# Rocket_PCB_true.net
KiCad netlist of a schematic drawn in EAGLE
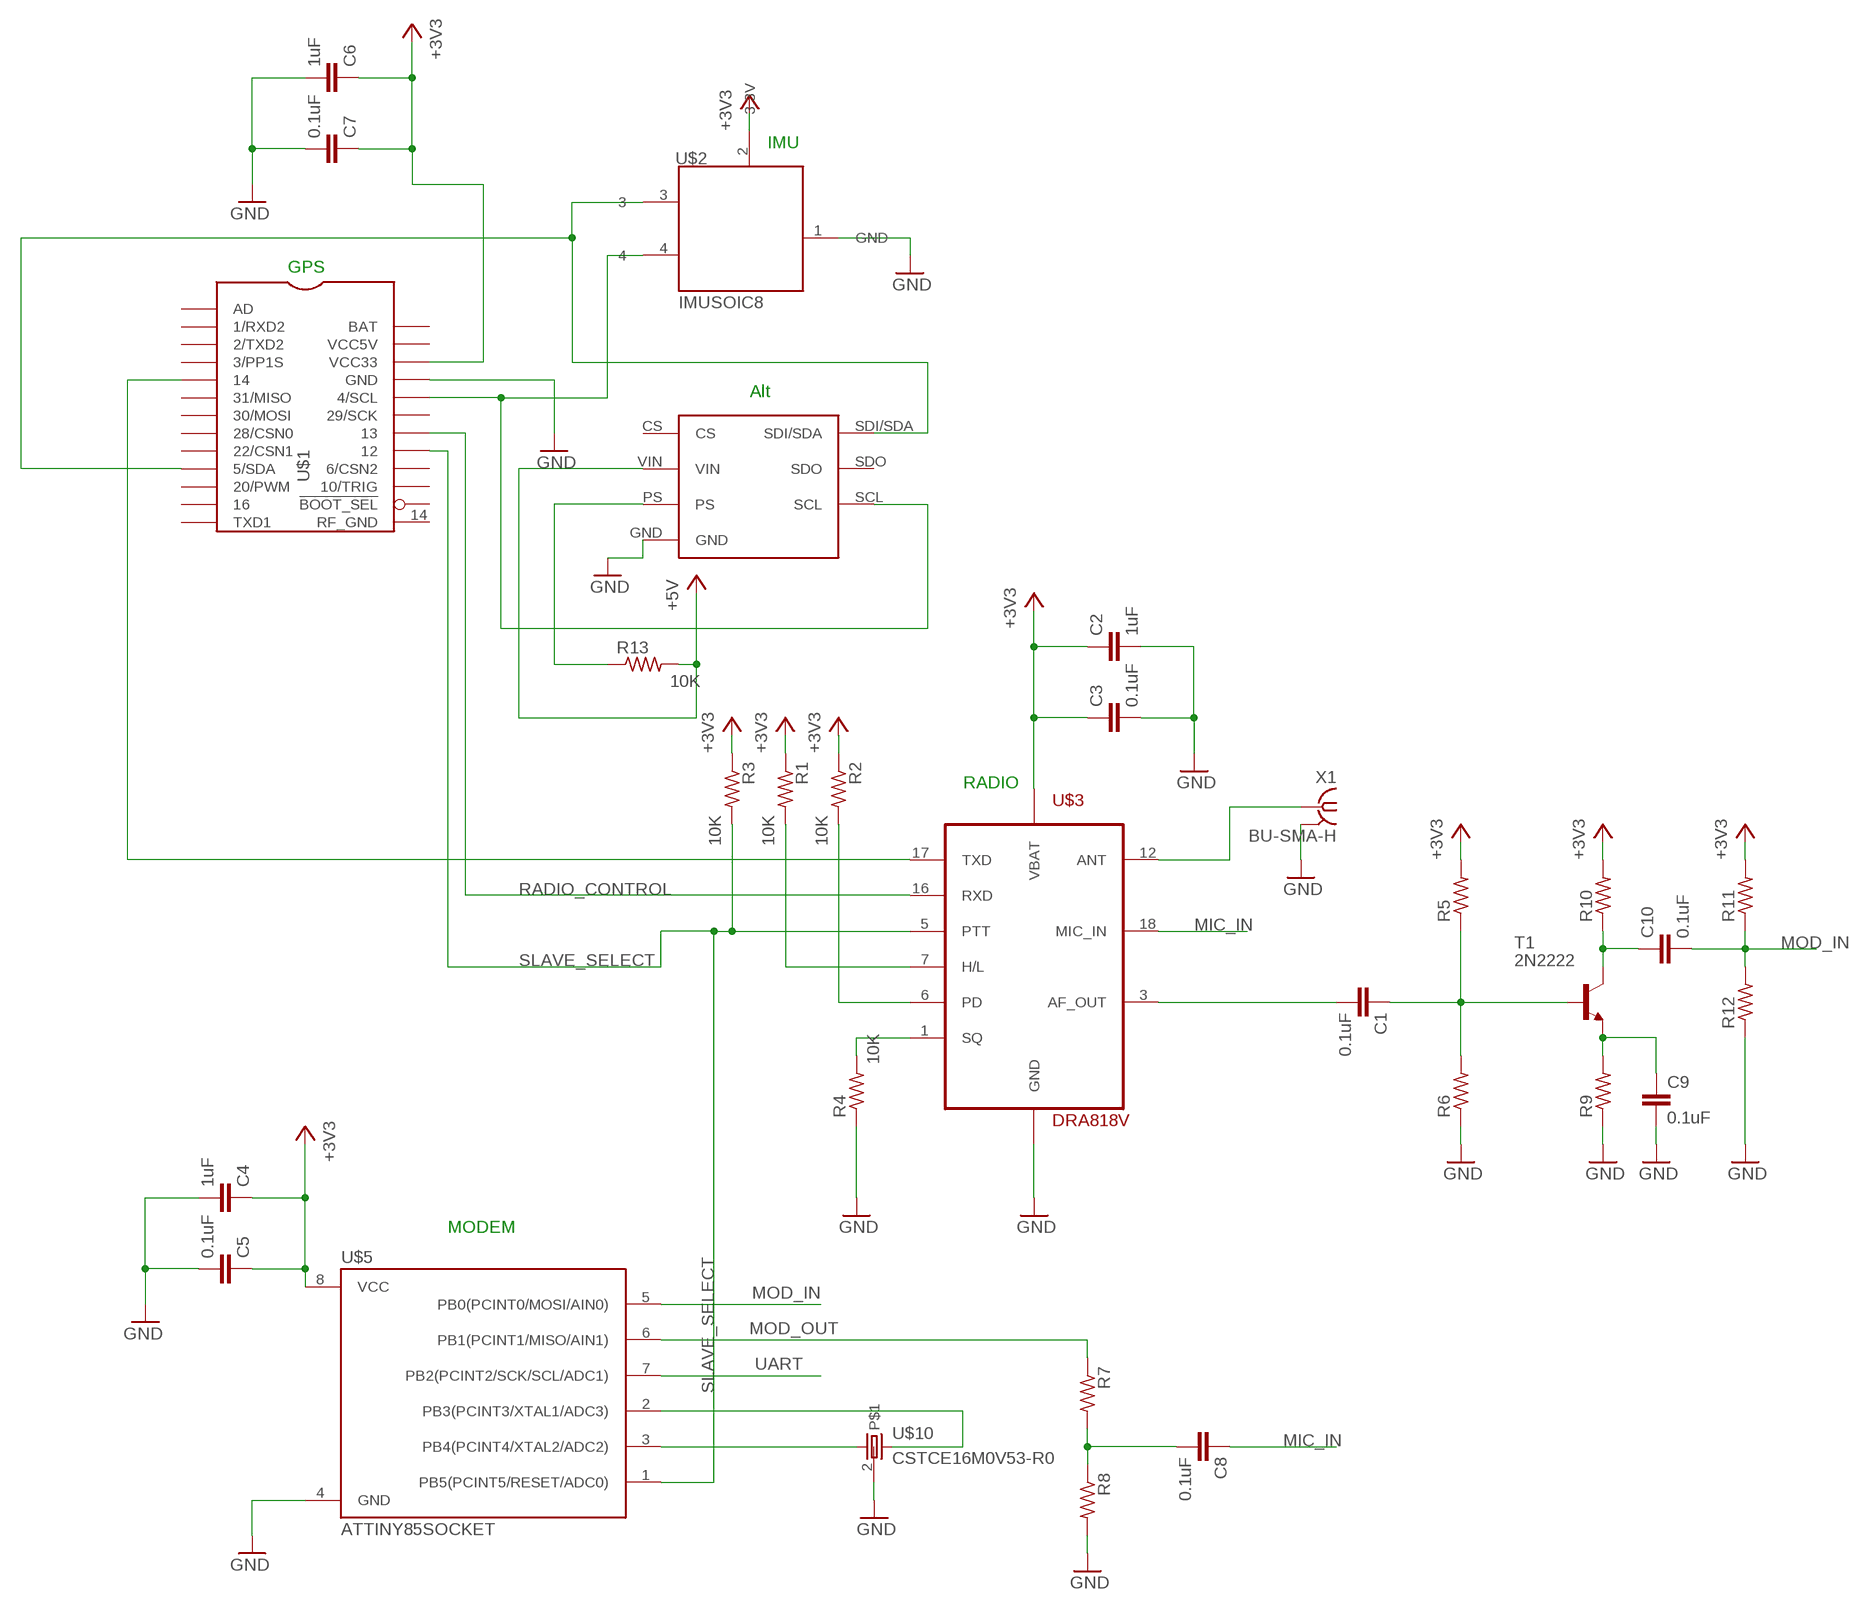
[diagram p0: schematic, sheet 1]

(export (version "E")
  (design (tool "Eeschema 10.0.6"))
  (components
    (comp (ref "C1")
      (value "0.1uF")
      (footprint "eagle-import:C0603")
      (libsource (lib "eagle-import") (part "C-EUC0603"))
    )
    (comp (ref "C2")
      (value "1uF")
      (footprint "eagle-import:C0603")
      (libsource (lib "eagle-import") (part "C-EUC0603"))
    )
    (comp (ref "C3")
      (value "0.1uF")
      (footprint "eagle-import:C0603")
      (libsource (lib "eagle-import") (part "C-EUC0603"))
    )
    (comp (ref "C4")
      (value "1uF")
      (footprint "eagle-import:C0603")
      (libsource (lib "eagle-import") (part "C-EUC0603"))
    )
    (comp (ref "C5")
      (value "0.1uF")
      (footprint "eagle-import:C0603")
      (libsource (lib "eagle-import") (part "C-EUC0603"))
    )
    (comp (ref "C6")
      (value "1uF")
      (footprint "eagle-import:C0603")
      (libsource (lib "eagle-import") (part "C-EUC0603"))
    )
    (comp (ref "C7")
      (value "0.1uF")
      (footprint "eagle-import:C0603")
      (libsource (lib "eagle-import") (part "C-EUC0603"))
    )
    (comp (ref "C8")
      (value "0.1uF")
      (footprint "eagle-import:C0603")
      (libsource (lib "eagle-import") (part "C-EUC0603"))
    )
    (comp (ref "C9")
      (value "0.1uF")
      (footprint "eagle-import:C0603")
      (libsource (lib "eagle-import") (part "C-EUC0603"))
    )
    (comp (ref "C10")
      (value "0.1uF")
      (footprint "eagle-import:C0603")
      (libsource (lib "eagle-import") (part "C-EUC0603"))
    )
    (comp (ref "R1")
      (value "10K")
      (footprint "eagle-import:R0603")
      (libsource (lib "eagle-import") (part "R-US_R0603"))
    )
    (comp (ref "R2")
      (value "10K")
      (footprint "eagle-import:R0603")
      (libsource (lib "eagle-import") (part "R-US_R0603"))
    )
    (comp (ref "R3")
      (value "10K")
      (footprint "eagle-import:R0603")
      (libsource (lib "eagle-import") (part "R-US_R0603"))
    )
    (comp (ref "R4")
      (value "10K")
      (footprint "eagle-import:R0603")
      (libsource (lib "eagle-import") (part "R-US_R0603"))
    )
    (comp (ref "R5")
      (value "R-US_R0603")
      (footprint "eagle-import:R0603")
      (libsource (lib "eagle-import") (part "R-US_R0603"))
    )
    (comp (ref "R6")
      (value "R-US_R0603")
      (footprint "eagle-import:R0603")
      (libsource (lib "eagle-import") (part "R-US_R0603"))
    )
    (comp (ref "R7")
      (value "R-US_R0603")
      (footprint "eagle-import:R0603")
      (libsource (lib "eagle-import") (part "R-US_R0603"))
    )
    (comp (ref "R8")
      (value "R-US_R0603")
      (footprint "eagle-import:R0603")
      (libsource (lib "eagle-import") (part "R-US_R0603"))
    )
    (comp (ref "R9")
      (value "R-US_R0603")
      (footprint "eagle-import:R0603")
      (libsource (lib "eagle-import") (part "R-US_R0603"))
    )
    (comp (ref "R10")
      (value "R-US_R0603")
      (footprint "eagle-import:R0603")
      (libsource (lib "eagle-import") (part "R-US_R0603"))
    )
    (comp (ref "R11")
      (value "R-US_R0603")
      (footprint "eagle-import:R0603")
      (libsource (lib "eagle-import") (part "R-US_R0603"))
    )
    (comp (ref "R12")
      (value "R-US_R0603")
      (footprint "eagle-import:R0603")
      (libsource (lib "eagle-import") (part "R-US_R0603"))
    )
    (comp (ref "R13")
      (value "10K")
      (footprint "eagle-import:R0603")
      (libsource (lib "eagle-import") (part "R-US_R0603"))
    )
    (comp (ref "T1")
      (value "2N2222")
      (footprint "eagle-import:TO18")
      (libsource (lib "eagle-import") (part "2N2222"))
    )
    (comp (ref "U$1")
      (value "NAVSPARK_FULL")
      (footprint "eagle-import:NAVSPARK_FULL")
      (libsource (lib "eagle-import") (part "NAVSPARK_FULL"))
    )
    (comp (ref "U$2")
      (value "IMUSOIC8")
      (footprint "eagle-import:SO08")
      (libsource (lib "eagle-import") (part "IMUSOIC8"))
    )
    (comp (ref "U$3")
      (value "DRA818V")
      (footprint "eagle-import:DORJI")
      (libsource (lib "eagle-import") (part "DORJIDRA818V"))
    )
    (comp (ref "U$4")
      (value "MS-5607")
      (footprint "eagle-import:MS-5607")
      (libsource (lib "eagle-import") (part "MS-5607"))
    )
    (comp (ref "U$5")
      (value "ATTINY85SOCKET")
      (footprint "eagle-import:SOCKET-08")
      (libsource (lib "eagle-import") (part "ATTINY85SOCKET"))
    )
    (comp (ref "U$10")
      (value "CSTCE16M0V53-R0")
      (footprint "eagle-import:MYSMD2_RESONATOR")
      (libsource (lib "eagle-import") (part "CSTCE16M0V53-R0"))
    )
    (comp (ref "X1")
      (value "BU-SMA-H")
      (footprint "eagle-import:BU-SMA-H")
      (libsource (lib "eagle-import") (part "BU-SMA-H"))
    )
  )
  (nets
    (net (code "1") (name "+3V3") (class "Default")
      (node (ref "C2") (pin "1") (pinfunction "1_1") (pintype "passive"))
      (node (ref "C3") (pin "1") (pinfunction "1_1") (pintype "passive"))
      (node (ref "C4") (pin "1") (pinfunction "1_1") (pintype "passive"))
      (node (ref "C5") (pin "1") (pinfunction "1_1") (pintype "passive"))
      (node (ref "C6") (pin "1") (pinfunction "1_1") (pintype "passive"))
      (node (ref "C7") (pin "1") (pinfunction "1_1") (pintype "passive"))
      (node (ref "R1") (pin "1") (pinfunction "1_1") (pintype "passive"))
      (node (ref "R10") (pin "2") (pinfunction "2_2") (pintype "passive"))
      (node (ref "R11") (pin "2") (pinfunction "2_2") (pintype "passive"))
      (node (ref "R2") (pin "1") (pinfunction "1_1") (pintype "passive"))
      (node (ref "R3") (pin "1") (pinfunction "1_1") (pintype "passive"))
      (node (ref "R5") (pin "2") (pinfunction "2_2") (pintype "passive"))
      (node (ref "U$1") (pin "23") (pinfunction "VCC33_23") (pintype "power_in"))
      (node (ref "U$3") (pin "8") (pinfunction "VBAT_8") (pintype "bidirectional"))
      (node (ref "U$5") (pin "8") (pinfunction "VCC_8") (pintype "bidirectional"))
    )
    (net (code "2") (name "+5V") (class "Default")
      (node (ref "R13") (pin "2") (pinfunction "2_2") (pintype "passive"))
      (node (ref "U$4") (pin "VIN") (pinfunction "VIN_VIN") (pintype "bidirectional"))
    )
    (net (code "3") (name "/BAT") (class "Default")
      (node (ref "U$1") (pin "25") (pinfunction "BAT_25") (pintype "power_in"))
    )
    (net (code "4") (name "/MIC_IN") (class "Default")
      (node (ref "C8") (pin "1") (pinfunction "1_1") (pintype "passive"))
      (node (ref "U$3") (pin "18") (pinfunction "MIC_IN_18") (pintype "bidirectional"))
    )
    (net (code "5") (name "/MOD_IN") (class "Default")
      (node (ref "C10") (pin "2") (pinfunction "2_2") (pintype "passive"))
      (node (ref "R11") (pin "1") (pinfunction "1_1") (pintype "passive"))
      (node (ref "R12") (pin "2") (pinfunction "2_2") (pintype "passive"))
      (node (ref "U$5") (pin "5") (pinfunction "PB0(PCINT0/MOSI/AIN0)_5") (pintype "bidirectional"))
    )
    (net (code "6") (name "/MOD_OUT") (class "Default")
      (node (ref "R7") (pin "1") (pinfunction "1_1") (pintype "passive"))
      (node (ref "U$5") (pin "6") (pinfunction "PB1(PCINT1/MISO/AIN1)_6") (pintype "bidirectional"))
    )
    (net (code "7") (name "/RADIO_CONTROL") (class "Default")
      (node (ref "U$1") (pin "19") (pinfunction "13_19") (pintype "bidirectional"))
      (node (ref "U$3") (pin "16") (pinfunction "RXD_16") (pintype "bidirectional"))
    )
    (net (code "8") (name "/RF_GND") (class "Default")
      (node (ref "U$1") (pin "14") (pinfunction "RF_GND_14") (pintype "power_in"))
    )
    (net (code "9") (name "/SLAVE_SELECT") (class "Default")
      (node (ref "R3") (pin "2") (pinfunction "2_2") (pintype "passive"))
      (node (ref "U$1") (pin "18") (pinfunction "12_18") (pintype "bidirectional"))
      (node (ref "U$3") (pin "5") (pinfunction "PTT_5") (pintype "bidirectional"))
      (node (ref "U$5") (pin "1") (pinfunction "PB5(PCINT5/RESET/ADC0)_1") (pintype "bidirectional"))
    )
    (net (code "10") (name "/UART") (class "Default")
      (node (ref "U$5") (pin "7") (pinfunction "PB2(PCINT2/SCK/SCL/ADC1)_7") (pintype "bidirectional"))
    )
    (net (code "11") (name "/VCC5V") (class "Default")
      (node (ref "U$1") (pin "24") (pinfunction "VCC5V_24") (pintype "power_in"))
    )
    (net (code "12") (name "GND") (class "Default")
      (node (ref "C2") (pin "2") (pinfunction "2_2") (pintype "passive"))
      (node (ref "C3") (pin "2") (pinfunction "2_2") (pintype "passive"))
      (node (ref "C4") (pin "2") (pinfunction "2_2") (pintype "passive"))
      (node (ref "C5") (pin "2") (pinfunction "2_2") (pintype "passive"))
      (node (ref "C6") (pin "2") (pinfunction "2_2") (pintype "passive"))
      (node (ref "C7") (pin "2") (pinfunction "2_2") (pintype "passive"))
      (node (ref "C9") (pin "2") (pinfunction "2_2") (pintype "passive"))
      (node (ref "R12") (pin "1") (pinfunction "1_1") (pintype "passive"))
      (node (ref "R4") (pin "1") (pinfunction "1_1") (pintype "passive"))
      (node (ref "R6") (pin "1") (pinfunction "1_1") (pintype "passive"))
      (node (ref "R8") (pin "2") (pinfunction "2_2") (pintype "passive"))
      (node (ref "R9") (pin "1") (pinfunction "1_1") (pintype "passive"))
      (node (ref "U$1") (pin "22") (pinfunction "GND_22") (pintype "power_in"))
      (node (ref "U$10") (pin "2") (pinfunction "P$1_2") (pintype "bidirectional"))
      (node (ref "U$3") (pin "10") (pinfunction "GND_10") (pintype "bidirectional"))
      (node (ref "U$3") (pin "9") (pinfunction "GND_9") (pintype "bidirectional"))
      (node (ref "U$4") (pin "GND") (pinfunction "GND_GND") (pintype "bidirectional"))
      (node (ref "U$5") (pin "4") (pinfunction "GND_4") (pintype "bidirectional"))
      (node (ref "X1") (pin "2") (pinfunction "2_2") (pintype "passive"))
      (node (ref "X1") (pin "3") (pinfunction "2_3") (pintype "passive"))
      (node (ref "X1") (pin "4") (pinfunction "2_4") (pintype "passive"))
      (node (ref "X1") (pin "5") (pinfunction "2_5") (pintype "passive"))
    )
    (net (code "13") (name "Net-(C8-Pad2)") (class "Default")
      (node (ref "C8") (pin "2") (pinfunction "2_2") (pintype "passive"))
      (node (ref "R7") (pin "2") (pinfunction "2_2") (pintype "passive"))
      (node (ref "R8") (pin "1") (pinfunction "1_1") (pintype "passive"))
    )
    (net (code "14") (name "Net-(R13-Pad1)") (class "Default")
      (node (ref "R13") (pin "1") (pinfunction "1_1") (pintype "passive"))
      (node (ref "U$4") (pin "PS") (pinfunction "PS_PS") (pintype "bidirectional"))
    )
    (net (code "15") (name "Net-(T1-B)") (class "Default")
      (node (ref "C1") (pin "1") (pinfunction "1_1") (pintype "passive"))
      (node (ref "R5") (pin "1") (pinfunction "1_1") (pintype "passive"))
      (node (ref "R6") (pin "2") (pinfunction "2_2") (pintype "passive"))
      (node (ref "T1") (pin "2") (pinfunction "B_2") (pintype "passive"))
    )
    (net (code "16") (name "Net-(T1-C)") (class "Default")
      (node (ref "C10") (pin "1") (pinfunction "1_1") (pintype "passive"))
      (node (ref "R10") (pin "1") (pinfunction "1_1") (pintype "passive"))
      (node (ref "T1") (pin "3") (pinfunction "C_3") (pintype "passive"))
    )
    (net (code "17") (name "Net-(T1-E)") (class "Default")
      (node (ref "C9") (pin "1") (pinfunction "1_1") (pintype "passive"))
      (node (ref "R9") (pin "2") (pinfunction "2_2") (pintype "passive"))
      (node (ref "T1") (pin "1") (pinfunction "E_1") (pintype "passive"))
    )
    (net (code "18") (name "Net-(U$1-4{slash}SCL)") (class "Default")
      (node (ref "U$1") (pin "21") (pinfunction "4/SCL_21") (pintype "bidirectional"))
      (node (ref "U$4") (pin "SCL") (pinfunction "SCL_SCL") (pintype "bidirectional"))
    )
    (net (code "19") (name "Net-(U$1-5{slash}SDA)") (class "Default")
      (node (ref "U$1") (pin "10") (pinfunction "5/SDA_10") (pintype "bidirectional"))
      (node (ref "U$4") (pin "SDI/SDA") (pinfunction "SDI/SDA_SDI/SDA") (pintype "bidirectional"))
    )
    (net (code "20") (name "Net-(U$1-14)") (class "Default")
      (node (ref "U$1") (pin "5") (pinfunction "14_5") (pintype "bidirectional"))
      (node (ref "U$3") (pin "17") (pinfunction "TXD_17") (pintype "bidirectional"))
    )
    (net (code "21") (name "Net-(U$3-AF_OUT)") (class "Default")
      (node (ref "C1") (pin "2") (pinfunction "2_2") (pintype "passive"))
      (node (ref "U$3") (pin "3") (pinfunction "AF_OUT_3") (pintype "bidirectional"))
    )
    (net (code "22") (name "Net-(U$3-ANT)") (class "Default")
      (node (ref "U$3") (pin "12") (pinfunction "ANT_12") (pintype "bidirectional"))
      (node (ref "X1") (pin "1") (pinfunction "1_1") (pintype "passive"))
    )
    (net (code "23") (name "Net-(U$3-H{slash}L)") (class "Default")
      (node (ref "R1") (pin "2") (pinfunction "2_2") (pintype "passive"))
      (node (ref "U$3") (pin "7") (pinfunction "H/L_7") (pintype "bidirectional"))
    )
    (net (code "24") (name "Net-(U$3-PD)") (class "Default")
      (node (ref "R2") (pin "2") (pinfunction "2_2") (pintype "passive"))
      (node (ref "U$3") (pin "6") (pinfunction "PD_6") (pintype "bidirectional"))
    )
    (net (code "25") (name "Net-(U$3-SQ)") (class "Default")
      (node (ref "R4") (pin "2") (pinfunction "2_2") (pintype "passive"))
      (node (ref "U$3") (pin "1") (pinfunction "SQ_1") (pintype "bidirectional"))
    )
    (net (code "26") (name "Net-(U$5-PB4(PCINT4{slash}XTAL2{slash}ADC2))") (class "Default")
      (node (ref "U$10") (pin "1") (pinfunction "1_1") (pintype "passive"))
      (node (ref "U$5") (pin "3") (pinfunction "PB4(PCINT4/XTAL2/ADC2)_3") (pintype "bidirectional"))
    )
    (net (code "27") (name "Net-(U$10-2)") (class "Default")
      (node (ref "U$10") (pin "3") (pinfunction "2_3") (pintype "passive"))
      (node (ref "U$5") (pin "2") (pinfunction "PB3(PCINT3/XTAL1/ADC3)_2") (pintype "bidirectional"))
    )
    (net (code "28") (name "unconnected-(U$1-1{slash}RXD2-Pad2)") (class "Default")
      (node (ref "U$1") (pin "2") (pinfunction "1/RXD2_2") (pintype "bidirectional"))
    )
    (net (code "29") (name "unconnected-(U$1-2{slash}TXD2-Pad3)") (class "Default")
      (node (ref "U$1") (pin "3") (pinfunction "2/TXD2_3") (pintype "bidirectional"))
    )
    (net (code "30") (name "unconnected-(U$1-3{slash}PP1S-Pad4)") (class "Default")
      (node (ref "U$1") (pin "4") (pinfunction "3/PP1S_4") (pintype "output"))
    )
    (net (code "31") (name "unconnected-(U$1-6{slash}CSN2-Pad17)") (class "Default")
      (node (ref "U$1") (pin "17") (pinfunction "6/CSN2_17") (pintype "bidirectional"))
    )
    (net (code "32") (name "unconnected-(U$1-10{slash}TRIG-Pad16)") (class "Default")
      (node (ref "U$1") (pin "16") (pinfunction "10/TRIG_16") (pintype "bidirectional"))
    )
    (net (code "33") (name "unconnected-(U$1-16-Pad12)") (class "Default")
      (node (ref "U$1") (pin "12") (pinfunction "16_12") (pintype "bidirectional"))
    )
    (net (code "34") (name "unconnected-(U$1-20{slash}PWM-Pad11)") (class "Default")
      (node (ref "U$1") (pin "11") (pinfunction "20/PWM_11") (pintype "bidirectional"))
    )
    (net (code "35") (name "unconnected-(U$1-22{slash}CSN1-Pad9)") (class "Default")
      (node (ref "U$1") (pin "9") (pinfunction "22/CSN1_9") (pintype "bidirectional"))
    )
    (net (code "36") (name "unconnected-(U$1-28{slash}CSN0-Pad8)") (class "Default")
      (node (ref "U$1") (pin "8") (pinfunction "28/CSN0_8") (pintype "bidirectional"))
    )
    (net (code "37") (name "unconnected-(U$1-29{slash}SCK-Pad20)") (class "Default")
      (node (ref "U$1") (pin "20") (pinfunction "29/SCK_20") (pintype "bidirectional"))
    )
    (net (code "38") (name "unconnected-(U$1-30{slash}MOSI-Pad7)") (class "Default")
      (node (ref "U$1") (pin "7") (pinfunction "30/MOSI_7") (pintype "bidirectional"))
    )
    (net (code "39") (name "unconnected-(U$1-31{slash}MISO-Pad6)") (class "Default")
      (node (ref "U$1") (pin "6") (pinfunction "31/MISO_6") (pintype "bidirectional"))
    )
    (net (code "40") (name "unconnected-(U$1-AD-Pad1)") (class "Default")
      (node (ref "U$1") (pin "1") (pinfunction "AD_1") (pintype "input"))
    )
    (net (code "41") (name "unconnected-(U$1-TXD1-Pad13)") (class "Default")
      (node (ref "U$1") (pin "13") (pinfunction "TXD1_13") (pintype "output"))
    )
    (net (code "42") (name "unconnected-(U$1-~{BOOT_SEL}-Pad15)") (class "Default")
      (node (ref "U$1") (pin "15") (pinfunction "~{BOOT_SEL}_15") (pintype "input"))
    )
    (net (code "43") (name "unconnected-(U$2-3.3V-Pad2)") (class "Default")
      (node (ref "U$2") (pin "2") (pinfunction "3.3V_2") (pintype "bidirectional"))
    )
    (net (code "44") (name "unconnected-(U$2-GND-Pad1)") (class "Default")
      (node (ref "U$2") (pin "1") (pinfunction "GND_1") (pintype "bidirectional"))
    )
    (net (code "45") (name "unconnected-(U$2-Pad3)") (class "Default")
      (node (ref "U$2") (pin "3") (pinfunction "3_3") (pintype "bidirectional"))
    )
    (net (code "46") (name "unconnected-(U$2-Pad4)") (class "Default")
      (node (ref "U$2") (pin "4") (pinfunction "4_4") (pintype "bidirectional"))
    )
    (net (code "47") (name "unconnected-(U$4-PadCS)") (class "Default")
      (node (ref "U$4") (pin "CS") (pinfunction "CS_CS") (pintype "bidirectional"))
    )
    (net (code "48") (name "unconnected-(U$4-PadSDO)") (class "Default")
      (node (ref "U$4") (pin "SDO") (pinfunction "SDO_SDO") (pintype "bidirectional"))
    )
  )
)
